# TSOP-Customized.net
KiCad netlist of a schematic drawn in EAGLE
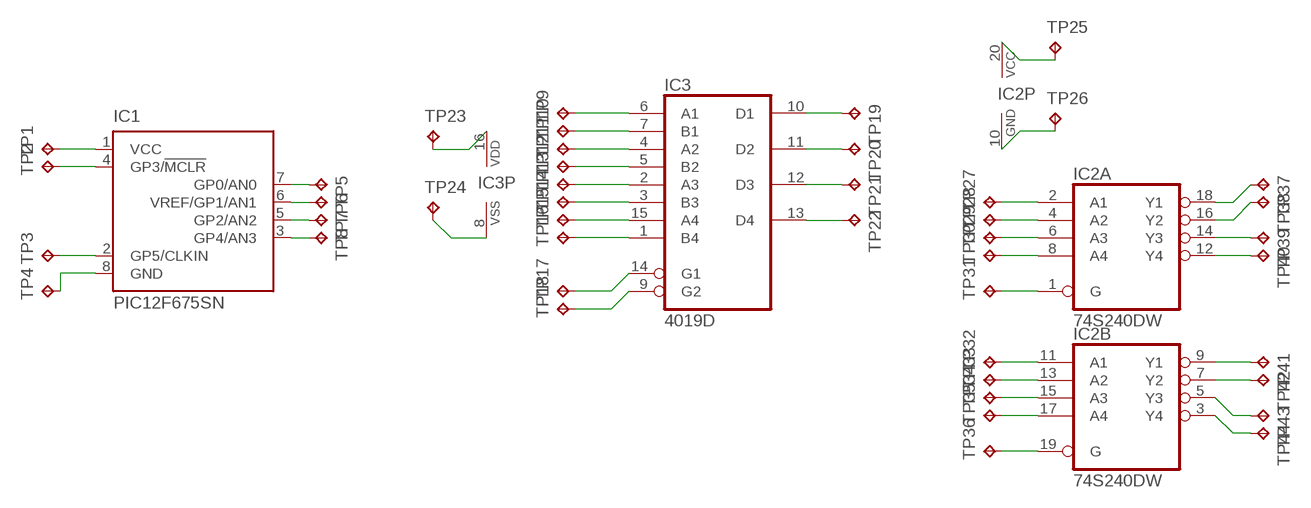
[diagram p0: schematic, sheet 1]

(export (version "E")
  (design (tool "Eeschema 10.0.6"))
  (components
    (comp (ref "IC1")
      (value "PIC12F675SN")
      (footprint "eagle-import:SO-08")
      (fields (field (name "MF") "MICROCHIP") (field (name "MPN") "PIC12F675-E/SN"))
      (libsource (lib "eagle-import") (part "PIC12F675SN"))
    )
    (comp (ref "IC2")
      (value "74S240DW")
      (footprint "eagle-import:SO20W")
      (libsource (lib "eagle-import") (part "74240DWS"))
    )
    (comp (ref "IC3")
      (value "4019D")
      (footprint "eagle-import:SO16")
      (libsource (lib "eagle-import") (part "4019D"))
    )
    (comp (ref "TP1")
      (value "TPPAD1-13Y")
      (footprint "eagle-import:P1-13Y")
      (libsource (lib "eagle-import") (part "TPPAD1-13Y"))
    )
    (comp (ref "TP2")
      (value "TPPAD1-13Y")
      (footprint "eagle-import:P1-13Y")
      (libsource (lib "eagle-import") (part "TPPAD1-13Y"))
    )
    (comp (ref "TP3")
      (value "TPPAD1-13Y")
      (footprint "eagle-import:P1-13Y")
      (libsource (lib "eagle-import") (part "TPPAD1-13Y"))
    )
    (comp (ref "TP4")
      (value "TPPAD1-13Y")
      (footprint "eagle-import:P1-13Y")
      (libsource (lib "eagle-import") (part "TPPAD1-13Y"))
    )
    (comp (ref "TP5")
      (value "TPPAD1-13Y")
      (footprint "eagle-import:P1-13Y")
      (libsource (lib "eagle-import") (part "TPPAD1-13Y"))
    )
    (comp (ref "TP6")
      (value "TPPAD1-13Y")
      (footprint "eagle-import:P1-13Y")
      (libsource (lib "eagle-import") (part "TPPAD1-13Y"))
    )
    (comp (ref "TP7")
      (value "TPPAD1-13Y")
      (footprint "eagle-import:P1-13Y")
      (libsource (lib "eagle-import") (part "TPPAD1-13Y"))
    )
    (comp (ref "TP8")
      (value "TPPAD1-13Y")
      (footprint "eagle-import:P1-13Y")
      (libsource (lib "eagle-import") (part "TPPAD1-13Y"))
    )
    (comp (ref "TP9")
      (value "TPPAD1-13Y")
      (footprint "eagle-import:P1-13Y")
      (libsource (lib "eagle-import") (part "TPPAD1-13Y"))
    )
    (comp (ref "TP10")
      (value "TPPAD1-13Y")
      (footprint "eagle-import:P1-13Y")
      (libsource (lib "eagle-import") (part "TPPAD1-13Y"))
    )
    (comp (ref "TP11")
      (value "TPPAD1-13Y")
      (footprint "eagle-import:P1-13Y")
      (libsource (lib "eagle-import") (part "TPPAD1-13Y"))
    )
    (comp (ref "TP12")
      (value "TPPAD1-13Y")
      (footprint "eagle-import:P1-13Y")
      (libsource (lib "eagle-import") (part "TPPAD1-13Y"))
    )
    (comp (ref "TP13")
      (value "TPPAD1-13Y")
      (footprint "eagle-import:P1-13Y")
      (libsource (lib "eagle-import") (part "TPPAD1-13Y"))
    )
    (comp (ref "TP14")
      (value "TPPAD1-13Y")
      (footprint "eagle-import:P1-13Y")
      (libsource (lib "eagle-import") (part "TPPAD1-13Y"))
    )
    (comp (ref "TP15")
      (value "TPPAD1-13Y")
      (footprint "eagle-import:P1-13Y")
      (libsource (lib "eagle-import") (part "TPPAD1-13Y"))
    )
    (comp (ref "TP16")
      (value "TPPAD1-13Y")
      (footprint "eagle-import:P1-13Y")
      (libsource (lib "eagle-import") (part "TPPAD1-13Y"))
    )
    (comp (ref "TP17")
      (value "TPPAD1-13Y")
      (footprint "eagle-import:P1-13Y")
      (libsource (lib "eagle-import") (part "TPPAD1-13Y"))
    )
    (comp (ref "TP18")
      (value "TPPAD1-13Y")
      (footprint "eagle-import:P1-13Y")
      (libsource (lib "eagle-import") (part "TPPAD1-13Y"))
    )
    (comp (ref "TP19")
      (value "TPPAD1-13Y")
      (footprint "eagle-import:P1-13Y")
      (libsource (lib "eagle-import") (part "TPPAD1-13Y"))
    )
    (comp (ref "TP20")
      (value "TPPAD1-13Y")
      (footprint "eagle-import:P1-13Y")
      (libsource (lib "eagle-import") (part "TPPAD1-13Y"))
    )
    (comp (ref "TP21")
      (value "TPPAD1-13Y")
      (footprint "eagle-import:P1-13Y")
      (libsource (lib "eagle-import") (part "TPPAD1-13Y"))
    )
    (comp (ref "TP22")
      (value "TPPAD1-13Y")
      (footprint "eagle-import:P1-13Y")
      (libsource (lib "eagle-import") (part "TPPAD1-13Y"))
    )
    (comp (ref "TP23")
      (value "TPPAD1-13Y")
      (footprint "eagle-import:P1-13Y")
      (libsource (lib "eagle-import") (part "TPPAD1-13Y"))
    )
    (comp (ref "TP24")
      (value "TPPAD1-13Y")
      (footprint "eagle-import:P1-13Y")
      (libsource (lib "eagle-import") (part "TPPAD1-13Y"))
    )
    (comp (ref "TP25")
      (value "TPPAD1-13Y")
      (footprint "eagle-import:P1-13Y")
      (libsource (lib "eagle-import") (part "TPPAD1-13Y"))
    )
    (comp (ref "TP26")
      (value "TPPAD1-13Y")
      (footprint "eagle-import:P1-13Y")
      (libsource (lib "eagle-import") (part "TPPAD1-13Y"))
    )
    (comp (ref "TP27")
      (value "TPPAD1-13Y")
      (footprint "eagle-import:P1-13Y")
      (libsource (lib "eagle-import") (part "TPPAD1-13Y"))
    )
    (comp (ref "TP28")
      (value "TPPAD1-13Y")
      (footprint "eagle-import:P1-13Y")
      (libsource (lib "eagle-import") (part "TPPAD1-13Y"))
    )
    (comp (ref "TP29")
      (value "TPPAD1-13Y")
      (footprint "eagle-import:P1-13Y")
      (libsource (lib "eagle-import") (part "TPPAD1-13Y"))
    )
    (comp (ref "TP30")
      (value "TPPAD1-13Y")
      (footprint "eagle-import:P1-13Y")
      (libsource (lib "eagle-import") (part "TPPAD1-13Y"))
    )
    (comp (ref "TP31")
      (value "TPPAD1-13Y")
      (footprint "eagle-import:P1-13Y")
      (libsource (lib "eagle-import") (part "TPPAD1-13Y"))
    )
    (comp (ref "TP32")
      (value "TPPAD1-13Y")
      (footprint "eagle-import:P1-13Y")
      (libsource (lib "eagle-import") (part "TPPAD1-13Y"))
    )
    (comp (ref "TP33")
      (value "TPPAD1-13Y")
      (footprint "eagle-import:P1-13Y")
      (libsource (lib "eagle-import") (part "TPPAD1-13Y"))
    )
    (comp (ref "TP34")
      (value "TPPAD1-13Y")
      (footprint "eagle-import:P1-13Y")
      (libsource (lib "eagle-import") (part "TPPAD1-13Y"))
    )
    (comp (ref "TP35")
      (value "TPPAD1-13Y")
      (footprint "eagle-import:P1-13Y")
      (libsource (lib "eagle-import") (part "TPPAD1-13Y"))
    )
    (comp (ref "TP36")
      (value "TPPAD1-13Y")
      (footprint "eagle-import:P1-13Y")
      (libsource (lib "eagle-import") (part "TPPAD1-13Y"))
    )
    (comp (ref "TP37")
      (value "TPPAD1-13Y")
      (footprint "eagle-import:P1-13Y")
      (libsource (lib "eagle-import") (part "TPPAD1-13Y"))
    )
    (comp (ref "TP38")
      (value "TPPAD1-13Y")
      (footprint "eagle-import:P1-13Y")
      (libsource (lib "eagle-import") (part "TPPAD1-13Y"))
    )
    (comp (ref "TP39")
      (value "TPPAD1-13Y")
      (footprint "eagle-import:P1-13Y")
      (libsource (lib "eagle-import") (part "TPPAD1-13Y"))
    )
    (comp (ref "TP40")
      (value "TPPAD1-13Y")
      (footprint "eagle-import:P1-13Y")
      (libsource (lib "eagle-import") (part "TPPAD1-13Y"))
    )
    (comp (ref "TP41")
      (value "TPPAD1-13Y")
      (footprint "eagle-import:P1-13Y")
      (libsource (lib "eagle-import") (part "TPPAD1-13Y"))
    )
    (comp (ref "TP42")
      (value "TPPAD1-13Y")
      (footprint "eagle-import:P1-13Y")
      (libsource (lib "eagle-import") (part "TPPAD1-13Y"))
    )
    (comp (ref "TP43")
      (value "TPPAD1-13Y")
      (footprint "eagle-import:P1-13Y")
      (libsource (lib "eagle-import") (part "TPPAD1-13Y"))
    )
    (comp (ref "TP44")
      (value "TPPAD1-13Y")
      (footprint "eagle-import:P1-13Y")
      (libsource (lib "eagle-import") (part "TPPAD1-13Y"))
    )
  )
  (nets
    (net (code "1") (name "Net-(IC1-GND)") (class "Default")
      (node (ref "IC1") (pin "8") (pinfunction "GND_8") (pintype "power_in"))
      (node (ref "TP4") (pin "TP") (pinfunction "TP_TP") (pintype "input"))
    )
    (net (code "2") (name "Net-(IC1-GP0{slash}AN0)") (class "Default")
      (node (ref "IC1") (pin "7") (pinfunction "GP0/AN0_7") (pintype "bidirectional"))
      (node (ref "TP5") (pin "TP") (pinfunction "TP_TP") (pintype "input"))
    )
    (net (code "3") (name "Net-(IC1-GP2{slash}AN2)") (class "Default")
      (node (ref "IC1") (pin "5") (pinfunction "GP2/AN2_5") (pintype "bidirectional"))
      (node (ref "TP7") (pin "TP") (pinfunction "TP_TP") (pintype "input"))
    )
    (net (code "4") (name "Net-(IC1-GP3{slash}~{MCLR})") (class "Default")
      (node (ref "IC1") (pin "4") (pinfunction "GP3/~{MCLR}_4") (pintype "input"))
      (node (ref "TP2") (pin "TP") (pinfunction "TP_TP") (pintype "input"))
    )
    (net (code "5") (name "Net-(IC1-GP4{slash}AN3)") (class "Default")
      (node (ref "IC1") (pin "3") (pinfunction "GP4/AN3_3") (pintype "bidirectional"))
      (node (ref "TP8") (pin "TP") (pinfunction "TP_TP") (pintype "input"))
    )
    (net (code "6") (name "Net-(IC1-GP5{slash}CLKIN)") (class "Default")
      (node (ref "IC1") (pin "2") (pinfunction "GP5/CLKIN_2") (pintype "bidirectional"))
      (node (ref "TP3") (pin "TP") (pinfunction "TP_TP") (pintype "input"))
    )
    (net (code "7") (name "Net-(IC1-VCC)") (class "Default")
      (node (ref "IC1") (pin "1") (pinfunction "VCC_1") (pintype "power_in"))
      (node (ref "TP1") (pin "TP") (pinfunction "TP_TP") (pintype "input"))
    )
    (net (code "8") (name "Net-(IC1-VREF{slash}GP1{slash}AN1)") (class "Default")
      (node (ref "IC1") (pin "6") (pinfunction "VREF/GP1/AN1_6") (pintype "bidirectional"))
      (node (ref "TP6") (pin "TP") (pinfunction "TP_TP") (pintype "input"))
    )
    (net (code "9") (name "Net-(IC2A-A1)") (class "Default")
      (node (ref "IC2") (pin "2") (pinfunction "A1_2") (pintype "input"))
      (node (ref "TP27") (pin "TP") (pinfunction "TP_TP") (pintype "input"))
    )
    (net (code "10") (name "Net-(IC2A-A2)") (class "Default")
      (node (ref "IC2") (pin "4") (pinfunction "A2_4") (pintype "input"))
      (node (ref "TP28") (pin "TP") (pinfunction "TP_TP") (pintype "input"))
    )
    (net (code "11") (name "Net-(IC2A-A3)") (class "Default")
      (node (ref "IC2") (pin "6") (pinfunction "A3_6") (pintype "input"))
      (node (ref "TP29") (pin "TP") (pinfunction "TP_TP") (pintype "input"))
    )
    (net (code "12") (name "Net-(IC2A-A4)") (class "Default")
      (node (ref "IC2") (pin "8") (pinfunction "A4_8") (pintype "input"))
      (node (ref "TP30") (pin "TP") (pinfunction "TP_TP") (pintype "input"))
    )
    (net (code "13") (name "Net-(IC2A-G)") (class "Default")
      (node (ref "IC2") (pin "1") (pinfunction "G_1") (pintype "input"))
      (node (ref "TP31") (pin "TP") (pinfunction "TP_TP") (pintype "input"))
    )
    (net (code "14") (name "Net-(IC2A-Y1)") (class "Default")
      (node (ref "IC2") (pin "18") (pinfunction "Y1_18") (pintype "tri_state"))
      (node (ref "TP37") (pin "TP") (pinfunction "TP_TP") (pintype "input"))
    )
    (net (code "15") (name "Net-(IC2A-Y2)") (class "Default")
      (node (ref "IC2") (pin "16") (pinfunction "Y2_16") (pintype "tri_state"))
      (node (ref "TP38") (pin "TP") (pinfunction "TP_TP") (pintype "input"))
    )
    (net (code "16") (name "Net-(IC2A-Y3)") (class "Default")
      (node (ref "IC2") (pin "14") (pinfunction "Y3_14") (pintype "tri_state"))
      (node (ref "TP39") (pin "TP") (pinfunction "TP_TP") (pintype "input"))
    )
    (net (code "17") (name "Net-(IC2A-Y4)") (class "Default")
      (node (ref "IC2") (pin "12") (pinfunction "Y4_12") (pintype "tri_state"))
      (node (ref "TP40") (pin "TP") (pinfunction "TP_TP") (pintype "input"))
    )
    (net (code "18") (name "Net-(IC2B-A1)") (class "Default")
      (node (ref "IC2") (pin "11") (pinfunction "A1_11") (pintype "input"))
      (node (ref "TP32") (pin "TP") (pinfunction "TP_TP") (pintype "input"))
    )
    (net (code "19") (name "Net-(IC2B-A2)") (class "Default")
      (node (ref "IC2") (pin "13") (pinfunction "A2_13") (pintype "input"))
      (node (ref "TP33") (pin "TP") (pinfunction "TP_TP") (pintype "input"))
    )
    (net (code "20") (name "Net-(IC2B-A3)") (class "Default")
      (node (ref "IC2") (pin "15") (pinfunction "A3_15") (pintype "input"))
      (node (ref "TP34") (pin "TP") (pinfunction "TP_TP") (pintype "input"))
    )
    (net (code "21") (name "Net-(IC2B-A4)") (class "Default")
      (node (ref "IC2") (pin "17") (pinfunction "A4_17") (pintype "input"))
      (node (ref "TP35") (pin "TP") (pinfunction "TP_TP") (pintype "input"))
    )
    (net (code "22") (name "Net-(IC2B-G)") (class "Default")
      (node (ref "IC2") (pin "19") (pinfunction "G_19") (pintype "input"))
      (node (ref "TP36") (pin "TP") (pinfunction "TP_TP") (pintype "input"))
    )
    (net (code "23") (name "Net-(IC2B-Y1)") (class "Default")
      (node (ref "IC2") (pin "9") (pinfunction "Y1_9") (pintype "tri_state"))
      (node (ref "TP41") (pin "TP") (pinfunction "TP_TP") (pintype "input"))
    )
    (net (code "24") (name "Net-(IC2B-Y2)") (class "Default")
      (node (ref "IC2") (pin "7") (pinfunction "Y2_7") (pintype "tri_state"))
      (node (ref "TP42") (pin "TP") (pinfunction "TP_TP") (pintype "input"))
    )
    (net (code "25") (name "Net-(IC2B-Y3)") (class "Default")
      (node (ref "IC2") (pin "5") (pinfunction "Y3_5") (pintype "tri_state"))
      (node (ref "TP43") (pin "TP") (pinfunction "TP_TP") (pintype "input"))
    )
    (net (code "26") (name "Net-(IC2B-Y4)") (class "Default")
      (node (ref "IC2") (pin "3") (pinfunction "Y4_3") (pintype "tri_state"))
      (node (ref "TP44") (pin "TP") (pinfunction "TP_TP") (pintype "input"))
    )
    (net (code "27") (name "Net-(IC2C-GND)") (class "Default")
      (node (ref "IC2") (pin "10") (pinfunction "GND_10") (pintype "power_in"))
      (node (ref "TP26") (pin "TP") (pinfunction "TP_TP") (pintype "input"))
    )
    (net (code "28") (name "Net-(IC2C-VCC)") (class "Default")
      (node (ref "IC2") (pin "20") (pinfunction "VCC_20") (pintype "power_in"))
      (node (ref "TP25") (pin "TP") (pinfunction "TP_TP") (pintype "input"))
    )
    (net (code "29") (name "Net-(IC3A-A1)") (class "Default")
      (node (ref "IC3") (pin "6") (pinfunction "A1_6") (pintype "input"))
      (node (ref "TP9") (pin "TP") (pinfunction "TP_TP") (pintype "input"))
    )
    (net (code "30") (name "Net-(IC3A-A2)") (class "Default")
      (node (ref "IC3") (pin "4") (pinfunction "A2_4") (pintype "input"))
      (node (ref "TP11") (pin "TP") (pinfunction "TP_TP") (pintype "input"))
    )
    (net (code "31") (name "Net-(IC3A-A3)") (class "Default")
      (node (ref "IC3") (pin "2") (pinfunction "A3_2") (pintype "input"))
      (node (ref "TP13") (pin "TP") (pinfunction "TP_TP") (pintype "input"))
    )
    (net (code "32") (name "Net-(IC3A-A4)") (class "Default")
      (node (ref "IC3") (pin "15") (pinfunction "A4_15") (pintype "input"))
      (node (ref "TP15") (pin "TP") (pinfunction "TP_TP") (pintype "input"))
    )
    (net (code "33") (name "Net-(IC3A-B1)") (class "Default")
      (node (ref "IC3") (pin "7") (pinfunction "B1_7") (pintype "input"))
      (node (ref "TP10") (pin "TP") (pinfunction "TP_TP") (pintype "input"))
    )
    (net (code "34") (name "Net-(IC3A-B2)") (class "Default")
      (node (ref "IC3") (pin "5") (pinfunction "B2_5") (pintype "input"))
      (node (ref "TP12") (pin "TP") (pinfunction "TP_TP") (pintype "input"))
    )
    (net (code "35") (name "Net-(IC3A-B3)") (class "Default")
      (node (ref "IC3") (pin "3") (pinfunction "B3_3") (pintype "input"))
      (node (ref "TP14") (pin "TP") (pinfunction "TP_TP") (pintype "input"))
    )
    (net (code "36") (name "Net-(IC3A-B4)") (class "Default")
      (node (ref "IC3") (pin "1") (pinfunction "B4_1") (pintype "input"))
      (node (ref "TP16") (pin "TP") (pinfunction "TP_TP") (pintype "input"))
    )
    (net (code "37") (name "Net-(IC3A-D1)") (class "Default")
      (node (ref "IC3") (pin "10") (pinfunction "D1_10") (pintype "output"))
      (node (ref "TP19") (pin "TP") (pinfunction "TP_TP") (pintype "input"))
    )
    (net (code "38") (name "Net-(IC3A-D2)") (class "Default")
      (node (ref "IC3") (pin "11") (pinfunction "D2_11") (pintype "output"))
      (node (ref "TP20") (pin "TP") (pinfunction "TP_TP") (pintype "input"))
    )
    (net (code "39") (name "Net-(IC3A-D3)") (class "Default")
      (node (ref "IC3") (pin "12") (pinfunction "D3_12") (pintype "output"))
      (node (ref "TP21") (pin "TP") (pinfunction "TP_TP") (pintype "input"))
    )
    (net (code "40") (name "Net-(IC3A-D4)") (class "Default")
      (node (ref "IC3") (pin "13") (pinfunction "D4_13") (pintype "output"))
      (node (ref "TP22") (pin "TP") (pinfunction "TP_TP") (pintype "input"))
    )
    (net (code "41") (name "Net-(IC3A-G1)") (class "Default")
      (node (ref "IC3") (pin "14") (pinfunction "G1_14") (pintype "input"))
      (node (ref "TP17") (pin "TP") (pinfunction "TP_TP") (pintype "input"))
    )
    (net (code "42") (name "Net-(IC3A-G2)") (class "Default")
      (node (ref "IC3") (pin "9") (pinfunction "G2_9") (pintype "input"))
      (node (ref "TP18") (pin "TP") (pinfunction "TP_TP") (pintype "input"))
    )
    (net (code "43") (name "Net-(IC3B-VDD)") (class "Default")
      (node (ref "IC3") (pin "16") (pinfunction "VDD_16") (pintype "power_in"))
      (node (ref "TP23") (pin "TP") (pinfunction "TP_TP") (pintype "input"))
    )
    (net (code "44") (name "Net-(IC3B-VSS)") (class "Default")
      (node (ref "IC3") (pin "8") (pinfunction "VSS_8") (pintype "power_in"))
      (node (ref "TP24") (pin "TP") (pinfunction "TP_TP") (pintype "input"))
    )
  )
)
